# Recevier.net
KiCad netlist of a schematic drawn in EAGLE
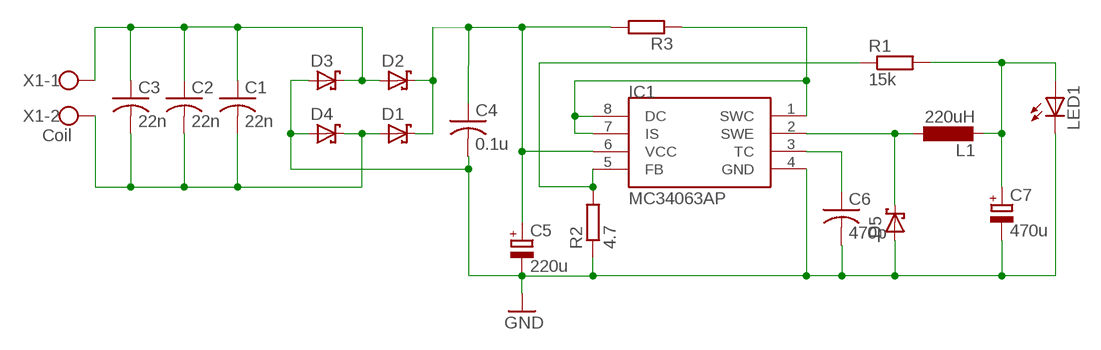
[diagram p0: schematic, sheet 1]

(export (version "E")
  (design (tool "Eeschema 10.0.6"))
  (components
    (comp (ref "C1")
      (value "22n")
      (footprint "eagle-import:C050-025X075")
      (libsource (lib "eagle-import") (part "C-US050-025X075"))
    )
    (comp (ref "C2")
      (value "22n")
      (footprint "eagle-import:C050-025X075")
      (libsource (lib "eagle-import") (part "C-US050-025X075"))
    )
    (comp (ref "C3")
      (value "22n")
      (footprint "eagle-import:C050-025X075")
      (libsource (lib "eagle-import") (part "C-US050-025X075"))
    )
    (comp (ref "C4")
      (value "0.1u")
      (footprint "eagle-import:C050-025X075")
      (libsource (lib "eagle-import") (part "C-US050-025X075"))
    )
    (comp (ref "C5")
      (value "220u")
      (footprint "eagle-import:E5-10,5")
      (libsource (lib "eagle-import") (part "CPOL-EUE5-10.5"))
    )
    (comp (ref "C6")
      (value "470p")
      (footprint "eagle-import:C050-025X075")
      (libsource (lib "eagle-import") (part "C-US050-025X075"))
    )
    (comp (ref "C7")
      (value "470u")
      (footprint "eagle-import:E3,5-8")
      (libsource (lib "eagle-import") (part "CPOL-EUE3.5-8"))
    )
    (comp (ref "D1")
      (value "1N5819-B")
      (footprint "eagle-import:DO41-7.6")
      (libsource (lib "eagle-import") (part "1N5819-B"))
    )
    (comp (ref "D2")
      (value "1N5819-B")
      (footprint "eagle-import:DO41-7.6")
      (libsource (lib "eagle-import") (part "1N5819-B"))
    )
    (comp (ref "D3")
      (value "1N5819-B")
      (footprint "eagle-import:DO41-7.6")
      (libsource (lib "eagle-import") (part "1N5819-B"))
    )
    (comp (ref "D4")
      (value "1N5819-B")
      (footprint "eagle-import:DO41-7.6")
      (libsource (lib "eagle-import") (part "1N5819-B"))
    )
    (comp (ref "D5")
      (value "1N5819-B")
      (footprint "eagle-import:DO41-7.6")
      (libsource (lib "eagle-import") (part "1N5819-B"))
    )
    (comp (ref "IC1")
      (value "MC34063AP")
      (footprint "eagle-import:DIL08")
      (libsource (lib "eagle-import") (part "MC34063AP"))
    )
    (comp (ref "L1")
      (value "220uH")
      (footprint "eagle-import:2200-12.7")
      (libsource (lib "eagle-import") (part "L-EU2200-12.7"))
    )
    (comp (ref "LED1")
      (value "LED3MM")
      (footprint "eagle-import:LED3MM")
      (libsource (lib "eagle-import") (part "LED3MM"))
    )
    (comp (ref "R1")
      (value "15k")
      (footprint "eagle-import:0207_10")
      (libsource (lib "eagle-import") (part "R-EU_0207/10"))
    )
    (comp (ref "R2")
      (value "4.7")
      (footprint "eagle-import:0207_10")
      (libsource (lib "eagle-import") (part "R-EU_0207/10"))
    )
    (comp (ref "R3")
      (value "R-EU_0207/10")
      (footprint "eagle-import:0207_10")
      (libsource (lib "eagle-import") (part "R-EU_0207/10"))
    )
    (comp (ref "X1")
      (value "Coil")
      (footprint "eagle-import:W237-102")
      (fields (field (name "MPN") "237-102"))
      (libsource (lib "eagle-import") (part "W237-102"))
    )
  )
  (nets
    (net (code "1") (name "GND") (class "Default")
      (node (ref "C4") (pin "2") (pinfunction "2_2") (pintype "passive"))
      (node (ref "C5") (pin "-") (pinfunction "-_-") (pintype "passive"))
      (node (ref "C6") (pin "2") (pinfunction "2_2") (pintype "passive"))
      (node (ref "C7") (pin "-") (pinfunction "-_-") (pintype "passive"))
      (node (ref "D3") (pin "A") (pinfunction "A_A") (pintype "passive"))
      (node (ref "D4") (pin "A") (pinfunction "A_A") (pintype "passive"))
      (node (ref "D5") (pin "A") (pinfunction "A_A") (pintype "passive"))
      (node (ref "IC1") (pin "4") (pinfunction "GND_4") (pintype "passive"))
      (node (ref "LED1") (pin "K") (pinfunction "C_K") (pintype "passive"))
      (node (ref "R2") (pin "1") (pinfunction "1_1") (pintype "passive"))
    )
    (net (code "2") (name "Net-(C7-Pad+)") (class "Default")
      (node (ref "C7") (pin "+") (pinfunction "+_+") (pintype "passive"))
      (node (ref "L1") (pin "2") (pinfunction "2_2") (pintype "passive"))
      (node (ref "LED1") (pin "A") (pinfunction "A_A") (pintype "passive"))
      (node (ref "R1") (pin "2") (pinfunction "2_2") (pintype "passive"))
    )
    (net (code "3") (name "Net-(IC1-DC)") (class "Default")
      (node (ref "IC1") (pin "1") (pinfunction "SWC_1") (pintype "passive"))
      (node (ref "IC1") (pin "7") (pinfunction "IS_7") (pintype "passive"))
      (node (ref "IC1") (pin "8") (pinfunction "DC_8") (pintype "passive"))
      (node (ref "R3") (pin "1") (pinfunction "1_1") (pintype "passive"))
    )
    (net (code "4") (name "Net-(IC1-FB)") (class "Default")
      (node (ref "IC1") (pin "5") (pinfunction "FB_5") (pintype "passive"))
      (node (ref "R1") (pin "1") (pinfunction "1_1") (pintype "passive"))
      (node (ref "R2") (pin "2") (pinfunction "2_2") (pintype "passive"))
    )
    (net (code "5") (name "Net-(IC1-SWE)") (class "Default")
      (node (ref "D5") (pin "C") (pinfunction "C_C") (pintype "passive"))
      (node (ref "IC1") (pin "2") (pinfunction "SWE_2") (pintype "passive"))
      (node (ref "L1") (pin "1") (pinfunction "1_1") (pintype "passive"))
    )
    (net (code "6") (name "Net-(IC1-TC)") (class "Default")
      (node (ref "C6") (pin "1") (pinfunction "1_1") (pintype "passive"))
      (node (ref "IC1") (pin "3") (pinfunction "TC_3") (pintype "passive"))
    )
    (net (code "7") (name "Net-(IC1-VCC)") (class "Default")
      (node (ref "C4") (pin "1") (pinfunction "1_1") (pintype "passive"))
      (node (ref "C5") (pin "+") (pinfunction "+_+") (pintype "passive"))
      (node (ref "D1") (pin "C") (pinfunction "C_C") (pintype "passive"))
      (node (ref "D2") (pin "C") (pinfunction "C_C") (pintype "passive"))
      (node (ref "IC1") (pin "6") (pinfunction "VCC_6") (pintype "passive"))
      (node (ref "R3") (pin "2") (pinfunction "2_2") (pintype "passive"))
    )
    (net (code "8") (name "Net-(X1A-KL)") (class "Default")
      (node (ref "C1") (pin "1") (pinfunction "1_1") (pintype "passive"))
      (node (ref "C2") (pin "1") (pinfunction "1_1") (pintype "passive"))
      (node (ref "C3") (pin "1") (pinfunction "1_1") (pintype "passive"))
      (node (ref "D2") (pin "A") (pinfunction "A_A") (pintype "passive"))
      (node (ref "D3") (pin "C") (pinfunction "C_C") (pintype "passive"))
      (node (ref "X1") (pin "1") (pinfunction "KL_1") (pintype "passive"))
    )
    (net (code "9") (name "Net-(X1B-KL)") (class "Default")
      (node (ref "C1") (pin "2") (pinfunction "2_2") (pintype "passive"))
      (node (ref "C2") (pin "2") (pinfunction "2_2") (pintype "passive"))
      (node (ref "C3") (pin "2") (pinfunction "2_2") (pintype "passive"))
      (node (ref "D1") (pin "A") (pinfunction "A_A") (pintype "passive"))
      (node (ref "D4") (pin "C") (pinfunction "C_C") (pintype "passive"))
      (node (ref "X1") (pin "2") (pinfunction "KL_2") (pintype "passive"))
    )
  )
)
